# Neopixel.net
KiCad netlist of a schematic drawn in Altium Designer
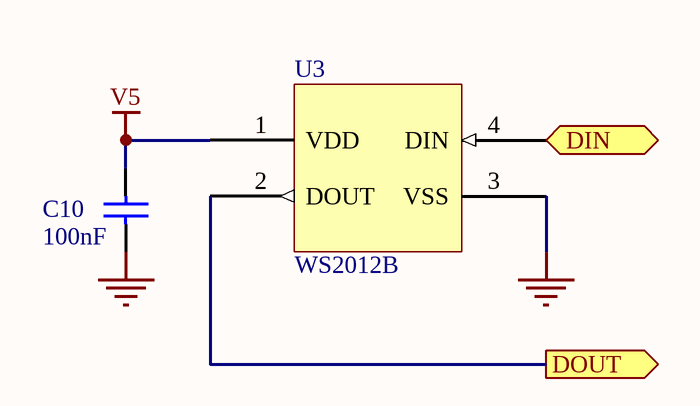
[diagram p0: Neopixel.SchDoc]

(export (version "E")
  (design (tool "Eeschema 10.0.6"))
  (components
    (comp (ref "C10")
      (value "100nF")
      (footprint "CAP0603")
      (description "Capacitor")
      (libsource (lib "Miscellaneous Devices") (part "Cap"))
    )
    (comp (ref "U3")
      (value "WS2012B")
      (footprint "WS2812b")
      (description "Neopixel")
      (libsource (lib "Components") (part "WS2012B"))
    )
  )
  (nets
    (net (code "1") (name "/DIN") (class "Default")
      (node (ref "U3") (pin "4") (pinfunction "DIN_4") (pintype "input"))
    )
    (net (code "2") (name "/DOUT") (class "Default")
      (node (ref "U3") (pin "2") (pinfunction "DOUT_2") (pintype "output"))
    )
    (net (code "3") (name "GND") (class "Default")
      (node (ref "C10") (pin "1") (pinfunction "1_1") (pintype "passive"))
      (node (ref "U3") (pin "3") (pinfunction "VSS_3") (pintype "passive"))
    )
    (net (code "4") (name "V5") (class "Default")
      (node (ref "C10") (pin "2") (pinfunction "2_2") (pintype "passive"))
      (node (ref "U3") (pin "1") (pinfunction "VDD_1") (pintype "power_in"))
    )
  )
)
